# Project3.net
KiCad netlist of a schematic drawn in EAGLE
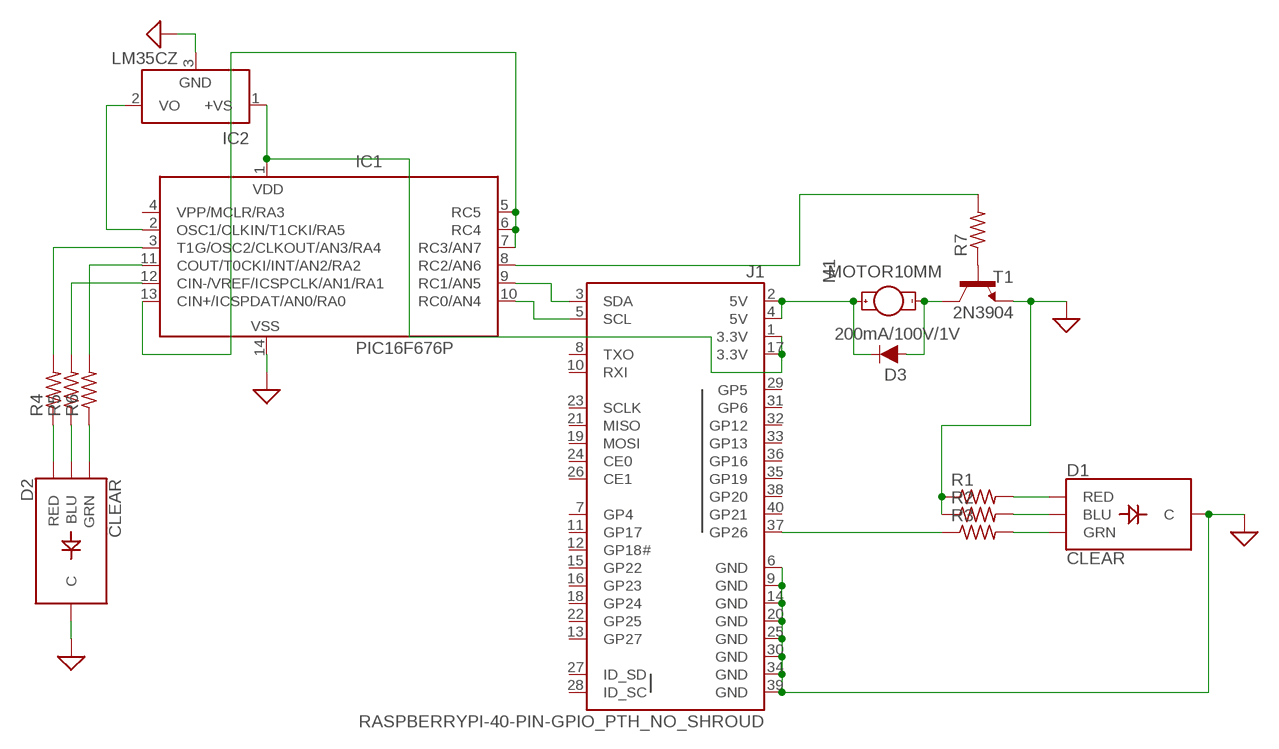
[diagram p0: schematic, sheet 1]

(export (version "E")
  (design (tool "Eeschema 10.0.6"))
  (components
    (comp (ref "D1")
      (value "CLEAR")
      (footprint "eagle-import:LED-RGB-THRU")
      (libsource (lib "eagle-import") (part "LED-RGB-CCCLEAR"))
    )
    (comp (ref "D2")
      (value "CLEAR")
      (footprint "eagle-import:LED-RGB-THRU")
      (libsource (lib "eagle-import") (part "LED-RGB-CCCLEAR"))
    )
    (comp (ref "D3")
      (value "200mA/100V/1V")
      (footprint "eagle-import:DIODE-1N4148")
      (libsource (lib "eagle-import") (part "DIODE-1N4148"))
    )
    (comp (ref "IC1")
      (value "PIC16F676P")
      (footprint "eagle-import:DIL14")
      (fields (field (name "MF") "MICROCHIP") (field (name "MPN") "PIC16F676-I/P"))
      (libsource (lib "eagle-import") (part "PIC16F676P"))
    )
    (comp (ref "IC2")
      (value "LM35CZ")
      (footprint "eagle-import:TO92")
      (libsource (lib "eagle-import") (part "LM35CZ"))
    )
    (comp (ref "J1")
      (value "RASPBERRYPI-40-PIN-GPIO_PTH_NO_SHROUD")
      (footprint "eagle-import:2X20")
      (libsource (lib "eagle-import") (part "RASPBERRYPI-40-PIN-GPIO_PTH_NO_SHROUD"))
    )
    (comp (ref "M1")
      (value "MOTOR10MM")
      (footprint "eagle-import:VIBE-MOTOR-10MM")
      (libsource (lib "eagle-import") (part "MOTOR10MM"))
    )
    (comp (ref "R1")
      (value "R-US_0204/2V")
      (footprint "eagle-import:0204V")
      (libsource (lib "eagle-import") (part "R-US_0204/2V"))
    )
    (comp (ref "R2")
      (value "R-US_0204/2V")
      (footprint "eagle-import:0204V")
      (libsource (lib "eagle-import") (part "R-US_0204/2V"))
    )
    (comp (ref "R3")
      (value "R-US_0204/2V")
      (footprint "eagle-import:0204V")
      (libsource (lib "eagle-import") (part "R-US_0204/2V"))
    )
    (comp (ref "R4")
      (value "R-US_0204/2V")
      (footprint "eagle-import:0204V")
      (libsource (lib "eagle-import") (part "R-US_0204/2V"))
    )
    (comp (ref "R5")
      (value "R-US_0204/2V")
      (footprint "eagle-import:0204V")
      (libsource (lib "eagle-import") (part "R-US_0204/2V"))
    )
    (comp (ref "R6")
      (value "R-US_0204/2V")
      (footprint "eagle-import:0204V")
      (libsource (lib "eagle-import") (part "R-US_0204/2V"))
    )
    (comp (ref "R7")
      (value "R-US_0204/2V")
      (footprint "eagle-import:0204V")
      (libsource (lib "eagle-import") (part "R-US_0204/2V"))
    )
    (comp (ref "T1")
      (value "2N3904")
      (footprint "eagle-import:TO92")
      (libsource (lib "eagle-import") (part "2N3904"))
    )
  )
  (nets
    (net (code "1") (name "Net-(D1-BLU)") (class "Default")
      (node (ref "D1") (pin "4") (pinfunction "BLU_4") (pintype "bidirectional"))
      (node (ref "R2") (pin "2") (pinfunction "2_2") (pintype "passive"))
    )
    (net (code "2") (name "Net-(D1-GRN)") (class "Default")
      (node (ref "D1") (pin "3") (pinfunction "GRN_3") (pintype "bidirectional"))
      (node (ref "R3") (pin "2") (pinfunction "2_2") (pintype "passive"))
    )
    (net (code "3") (name "Net-(D1-RED)") (class "Default")
      (node (ref "D1") (pin "1") (pinfunction "RED_1") (pintype "bidirectional"))
      (node (ref "R1") (pin "2") (pinfunction "2_2") (pintype "passive"))
    )
    (net (code "4") (name "Net-(D2-BLU)") (class "Default")
      (node (ref "D2") (pin "4") (pinfunction "BLU_4") (pintype "bidirectional"))
      (node (ref "R5") (pin "1") (pinfunction "1_1") (pintype "passive"))
    )
    (net (code "5") (name "Net-(D2-GRN)") (class "Default")
      (node (ref "D2") (pin "3") (pinfunction "GRN_3") (pintype "bidirectional"))
      (node (ref "R6") (pin "1") (pinfunction "1_1") (pintype "passive"))
    )
    (net (code "6") (name "Net-(D2-RED)") (class "Default")
      (node (ref "D2") (pin "1") (pinfunction "RED_1") (pintype "bidirectional"))
      (node (ref "R4") (pin "1") (pinfunction "1_1") (pintype "passive"))
    )
    (net (code "7") (name "Net-(D3-PadC)") (class "Default")
      (node (ref "D3") (pin "C") (pinfunction "C_C") (pintype "passive"))
      (node (ref "J1") (pin "2") (pinfunction "5V_2") (pintype "power_in"))
      (node (ref "J1") (pin "4") (pinfunction "5V_4") (pintype "power_in"))
      (node (ref "M1") (pin "+") (pinfunction "+_+") (pintype "bidirectional"))
    )
    (net (code "8") (name "Net-(IC1-CIN+{slash}ICSPDAT{slash}AN0{slash}RA0)") (class "Default")
      (node (ref "IC1") (pin "13") (pinfunction "CIN+/ICSPDAT/AN0/RA0_13") (pintype "bidirectional"))
      (node (ref "IC1") (pin "5") (pinfunction "RC5_5") (pintype "bidirectional"))
      (node (ref "IC1") (pin "6") (pinfunction "RC4_6") (pintype "bidirectional"))
      (node (ref "IC1") (pin "7") (pinfunction "RC3/AN7_7") (pintype "bidirectional"))
    )
    (net (code "9") (name "Net-(IC1-CIN-{slash}VREF{slash}ICSPCLK{slash}AN1{slash}RA1)") (class "Default")
      (node (ref "IC1") (pin "12") (pinfunction "CIN-/VREF/ICSPCLK/AN1/RA1_12") (pintype "bidirectional"))
      (node (ref "R5") (pin "2") (pinfunction "2_2") (pintype "passive"))
    )
    (net (code "10") (name "Net-(IC1-COUT{slash}T0CKI{slash}INT{slash}AN2{slash}RA2)") (class "Default")
      (node (ref "IC1") (pin "11") (pinfunction "COUT/T0CKI/INT/AN2/RA2_11") (pintype "bidirectional"))
      (node (ref "R6") (pin "2") (pinfunction "2_2") (pintype "passive"))
    )
    (net (code "11") (name "Net-(IC1-OSC1{slash}CLKIN{slash}T1CKI{slash}RA5)") (class "Default")
      (node (ref "IC1") (pin "2") (pinfunction "OSC1/CLKIN/T1CKI/RA5_2") (pintype "bidirectional"))
      (node (ref "IC2") (pin "2") (pinfunction "VO_2") (pintype "input"))
    )
    (net (code "12") (name "Net-(IC1-RC0{slash}AN4)") (class "Default")
      (node (ref "IC1") (pin "10") (pinfunction "RC0/AN4_10") (pintype "bidirectional"))
      (node (ref "J1") (pin "5") (pinfunction "SCL_5") (pintype "bidirectional"))
    )
    (net (code "13") (name "Net-(IC1-RC1{slash}AN5)") (class "Default")
      (node (ref "IC1") (pin "9") (pinfunction "RC1/AN5_9") (pintype "bidirectional"))
      (node (ref "J1") (pin "3") (pinfunction "SDA_3") (pintype "bidirectional"))
    )
    (net (code "14") (name "Net-(IC1-RC2{slash}AN6)") (class "Default")
      (node (ref "IC1") (pin "8") (pinfunction "RC2/AN6_8") (pintype "bidirectional"))
      (node (ref "R7") (pin "2") (pinfunction "2_2") (pintype "passive"))
    )
    (net (code "15") (name "Net-(IC1-T1G{slash}OSC2{slash}CLKOUT{slash}AN3{slash}RA4)") (class "Default")
      (node (ref "IC1") (pin "3") (pinfunction "T1G/OSC2/CLKOUT/AN3/RA4_3") (pintype "bidirectional"))
      (node (ref "R4") (pin "2") (pinfunction "2_2") (pintype "passive"))
    )
    (net (code "16") (name "Net-(IC1-VDD)") (class "Default")
      (node (ref "IC1") (pin "1") (pinfunction "VDD_1") (pintype "power_in"))
      (node (ref "IC2") (pin "1") (pinfunction "+VS_1") (pintype "input"))
      (node (ref "J1") (pin "1") (pinfunction "3.3V_1") (pintype "power_in"))
      (node (ref "J1") (pin "17") (pinfunction "3.3V_17") (pintype "power_in"))
    )
    (net (code "17") (name "Net-(J1-GP26)") (class "Default")
      (node (ref "J1") (pin "37") (pinfunction "GP26_37") (pintype "bidirectional"))
      (node (ref "R3") (pin "1") (pinfunction "1_1") (pintype "passive"))
    )
    (net (code "18") (name "Net-(T1-B)") (class "Default")
      (node (ref "R7") (pin "1") (pinfunction "1_1") (pintype "passive"))
      (node (ref "T1") (pin "2") (pinfunction "B_2") (pintype "passive"))
    )
    (net (code "19") (name "Net-(T1-C)") (class "Default")
      (node (ref "D3") (pin "A") (pinfunction "A_A") (pintype "passive"))
      (node (ref "M1") (pin "-") (pinfunction "-_-") (pintype "bidirectional"))
      (node (ref "T1") (pin "1") (pinfunction "C_1") (pintype "passive"))
    )
    (net (code "20") (name "SUP") (class "Default")
      (node (ref "D1") (pin "2") (pinfunction "C_2") (pintype "bidirectional"))
      (node (ref "D2") (pin "2") (pinfunction "C_2") (pintype "bidirectional"))
      (node (ref "IC1") (pin "14") (pinfunction "VSS_14") (pintype "power_in"))
      (node (ref "IC2") (pin "3") (pinfunction "GND_3") (pintype "power_in"))
      (node (ref "J1") (pin "14") (pinfunction "GND_14") (pintype "power_in"))
      (node (ref "J1") (pin "20") (pinfunction "GND_20") (pintype "power_in"))
      (node (ref "J1") (pin "25") (pinfunction "GND_25") (pintype "power_in"))
      (node (ref "J1") (pin "30") (pinfunction "GND_30") (pintype "power_in"))
      (node (ref "J1") (pin "34") (pinfunction "GND_34") (pintype "power_in"))
      (node (ref "J1") (pin "39") (pinfunction "GND_39") (pintype "power_in"))
      (node (ref "J1") (pin "6") (pinfunction "GND_6") (pintype "power_in"))
      (node (ref "J1") (pin "9") (pinfunction "GND_9") (pintype "power_in"))
      (node (ref "R1") (pin "1") (pinfunction "1_1") (pintype "passive"))
      (node (ref "R2") (pin "1") (pinfunction "1_1") (pintype "passive"))
      (node (ref "T1") (pin "3") (pinfunction "E_3") (pintype "passive"))
    )
    (net (code "21") (name "unconnected-(IC1-VPP{slash}MCLR{slash}RA3-Pad4)") (class "Default")
      (node (ref "IC1") (pin "4") (pinfunction "VPP/MCLR/RA3_4") (pintype "input"))
    )
    (net (code "22") (name "unconnected-(J1-CE0-Pad24)") (class "Default")
      (node (ref "J1") (pin "24") (pinfunction "CE0_24") (pintype "output"))
    )
    (net (code "23") (name "unconnected-(J1-CE1-Pad26)") (class "Default")
      (node (ref "J1") (pin "26") (pinfunction "CE1_26") (pintype "output"))
    )
    (net (code "24") (name "unconnected-(J1-GP4-Pad7)") (class "Default")
      (node (ref "J1") (pin "7") (pinfunction "GP4_7") (pintype "bidirectional"))
    )
    (net (code "25") (name "unconnected-(J1-GP5-Pad29)") (class "Default")
      (node (ref "J1") (pin "29") (pinfunction "GP5_29") (pintype "bidirectional"))
    )
    (net (code "26") (name "unconnected-(J1-GP6-Pad31)") (class "Default")
      (node (ref "J1") (pin "31") (pinfunction "GP6_31") (pintype "bidirectional"))
    )
    (net (code "27") (name "unconnected-(J1-GP12-Pad32)") (class "Default")
      (node (ref "J1") (pin "32") (pinfunction "GP12_32") (pintype "bidirectional"))
    )
    (net (code "28") (name "unconnected-(J1-GP13-Pad33)") (class "Default")
      (node (ref "J1") (pin "33") (pinfunction "GP13_33") (pintype "bidirectional"))
    )
    (net (code "29") (name "unconnected-(J1-GP16-Pad36)") (class "Default")
      (node (ref "J1") (pin "36") (pinfunction "GP16_36") (pintype "bidirectional"))
    )
    (net (code "30") (name "unconnected-(J1-GP17-Pad11)") (class "Default")
      (node (ref "J1") (pin "11") (pinfunction "GP17_11") (pintype "bidirectional"))
    )
    (net (code "31") (name "unconnected-(J1-GP18#-Pad12)") (class "Default")
      (node (ref "J1") (pin "12") (pinfunction "GP18#_12") (pintype "bidirectional"))
    )
    (net (code "32") (name "unconnected-(J1-GP19-Pad35)") (class "Default")
      (node (ref "J1") (pin "35") (pinfunction "GP19_35") (pintype "bidirectional"))
    )
    (net (code "33") (name "unconnected-(J1-GP20-Pad38)") (class "Default")
      (node (ref "J1") (pin "38") (pinfunction "GP20_38") (pintype "bidirectional"))
    )
    (net (code "34") (name "unconnected-(J1-GP21-Pad40)") (class "Default")
      (node (ref "J1") (pin "40") (pinfunction "GP21_40") (pintype "bidirectional"))
    )
    (net (code "35") (name "unconnected-(J1-GP22-Pad15)") (class "Default")
      (node (ref "J1") (pin "15") (pinfunction "GP22_15") (pintype "bidirectional"))
    )
    (net (code "36") (name "unconnected-(J1-GP23-Pad16)") (class "Default")
      (node (ref "J1") (pin "16") (pinfunction "GP23_16") (pintype "bidirectional"))
    )
    (net (code "37") (name "unconnected-(J1-GP24-Pad18)") (class "Default")
      (node (ref "J1") (pin "18") (pinfunction "GP24_18") (pintype "bidirectional"))
    )
    (net (code "38") (name "unconnected-(J1-GP25-Pad22)") (class "Default")
      (node (ref "J1") (pin "22") (pinfunction "GP25_22") (pintype "bidirectional"))
    )
    (net (code "39") (name "unconnected-(J1-GP27-Pad13)") (class "Default")
      (node (ref "J1") (pin "13") (pinfunction "GP27_13") (pintype "bidirectional"))
    )
    (net (code "40") (name "unconnected-(J1-ID_SC-Pad28)") (class "Default")
      (node (ref "J1") (pin "28") (pinfunction "ID_SC_28") (pintype "bidirectional"))
    )
    (net (code "41") (name "unconnected-(J1-ID_SD-Pad27)") (class "Default")
      (node (ref "J1") (pin "27") (pinfunction "ID_SD_27") (pintype "bidirectional"))
    )
    (net (code "42") (name "unconnected-(J1-MISO-Pad21)") (class "Default")
      (node (ref "J1") (pin "21") (pinfunction "MISO_21") (pintype "input"))
    )
    (net (code "43") (name "unconnected-(J1-MOSI-Pad19)") (class "Default")
      (node (ref "J1") (pin "19") (pinfunction "MOSI_19") (pintype "output"))
    )
    (net (code "44") (name "unconnected-(J1-RXI-Pad10)") (class "Default")
      (node (ref "J1") (pin "10") (pinfunction "RXI_10") (pintype "input"))
    )
    (net (code "45") (name "unconnected-(J1-SCLK-Pad23)") (class "Default")
      (node (ref "J1") (pin "23") (pinfunction "SCLK_23") (pintype "output"))
    )
    (net (code "46") (name "unconnected-(J1-TXO-Pad8)") (class "Default")
      (node (ref "J1") (pin "8") (pinfunction "TXO_8") (pintype "output"))
    )
  )
)
